# odrive-hat.net
KiCad netlist of a schematic drawn in EAGLE
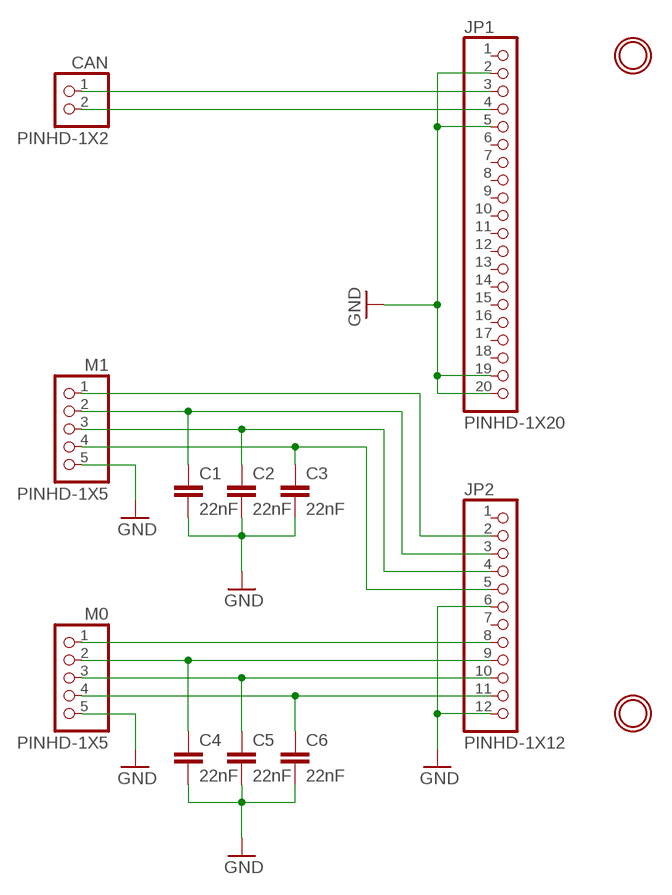
[diagram p0: schematic, sheet 1]

(export (version "E")
  (design (tool "Eeschema 10.0.6"))
  (components
    (comp (ref "C1")
      (value "22nF")
      (footprint "eagle-import:C0603")
      (libsource (lib "eagle-import") (part "C-EUC0603"))
    )
    (comp (ref "C2")
      (value "22nF")
      (footprint "eagle-import:C0603")
      (libsource (lib "eagle-import") (part "C-EUC0603"))
    )
    (comp (ref "C3")
      (value "22nF")
      (footprint "eagle-import:C0603")
      (libsource (lib "eagle-import") (part "C-EUC0603"))
    )
    (comp (ref "C4")
      (value "22nF")
      (footprint "eagle-import:C0603")
      (libsource (lib "eagle-import") (part "C-EUC0603"))
    )
    (comp (ref "C5")
      (value "22nF")
      (footprint "eagle-import:C0603")
      (libsource (lib "eagle-import") (part "C-EUC0603"))
    )
    (comp (ref "C6")
      (value "22nF")
      (footprint "eagle-import:C0603")
      (libsource (lib "eagle-import") (part "C-EUC0603"))
    )
    (comp (ref "CAN")
      (value "PINHD-1X2")
      (footprint "eagle-import:1X02")
      (libsource (lib "eagle-import") (part "PINHD-1X2"))
    )
    (comp (ref "JP1")
      (value "PINHD-1X20")
      (footprint "eagle-import:1X20")
      (libsource (lib "eagle-import") (part "PINHD-1X20"))
    )
    (comp (ref "JP2")
      (value "PINHD-1X12")
      (footprint "eagle-import:1X12")
      (libsource (lib "eagle-import") (part "PINHD-1X12"))
    )
    (comp (ref "M0")
      (value "PINHD-1X5")
      (footprint "eagle-import:1X05")
      (libsource (lib "eagle-import") (part "PINHD-1X5"))
    )
    (comp (ref "M1")
      (value "PINHD-1X5")
      (footprint "eagle-import:1X05")
      (libsource (lib "eagle-import") (part "PINHD-1X5"))
    )
    (comp (ref "U$1")
      (value "MICROBUILDER_MOUNTINGHOLE3.0THIN")
      (footprint "eagle-import:MICROBUILDER_MOUNTINGHOLE_3.0_PLATEDTHIN")
      (libsource (lib "eagle-import") (part "MICROBUILDER_MOUNTINGHOLE3.0THIN"))
    )
    (comp (ref "U$2")
      (value "MICROBUILDER_MOUNTINGHOLE3.0THIN")
      (footprint "eagle-import:MICROBUILDER_MOUNTINGHOLE_3.0_PLATEDTHIN")
      (libsource (lib "eagle-import") (part "MICROBUILDER_MOUNTINGHOLE3.0THIN"))
    )
  )
  (nets
    (net (code "1") (name "GND") (class "Default")
      (node (ref "C1") (pin "2") (pinfunction "2_2") (pintype "passive"))
      (node (ref "C2") (pin "2") (pinfunction "2_2") (pintype "passive"))
      (node (ref "C3") (pin "2") (pinfunction "2_2") (pintype "passive"))
      (node (ref "C4") (pin "2") (pinfunction "2_2") (pintype "passive"))
      (node (ref "C5") (pin "2") (pinfunction "2_2") (pintype "passive"))
      (node (ref "C6") (pin "2") (pinfunction "2_2") (pintype "passive"))
      (node (ref "JP1") (pin "19") (pinfunction "19_19") (pintype "passive"))
      (node (ref "JP1") (pin "2") (pinfunction "2_2") (pintype "passive"))
      (node (ref "JP1") (pin "20") (pinfunction "20_20") (pintype "passive"))
      (node (ref "JP1") (pin "5") (pinfunction "5_5") (pintype "passive"))
      (node (ref "JP2") (pin "12") (pinfunction "12_12") (pintype "passive"))
      (node (ref "JP2") (pin "6") (pinfunction "6_6") (pintype "passive"))
      (node (ref "M0") (pin "5") (pinfunction "5_5") (pintype "passive"))
      (node (ref "M1") (pin "5") (pinfunction "5_5") (pintype "passive"))
    )
    (net (code "2") (name "Net-(C1-Pad1)") (class "Default")
      (node (ref "C1") (pin "1") (pinfunction "1_1") (pintype "passive"))
      (node (ref "JP2") (pin "3") (pinfunction "3_3") (pintype "passive"))
      (node (ref "M1") (pin "2") (pinfunction "2_2") (pintype "passive"))
    )
    (net (code "3") (name "Net-(C2-Pad1)") (class "Default")
      (node (ref "C2") (pin "1") (pinfunction "1_1") (pintype "passive"))
      (node (ref "JP2") (pin "4") (pinfunction "4_4") (pintype "passive"))
      (node (ref "M1") (pin "3") (pinfunction "3_3") (pintype "passive"))
    )
    (net (code "4") (name "Net-(C3-Pad1)") (class "Default")
      (node (ref "C3") (pin "1") (pinfunction "1_1") (pintype "passive"))
      (node (ref "JP2") (pin "5") (pinfunction "5_5") (pintype "passive"))
      (node (ref "M1") (pin "4") (pinfunction "4_4") (pintype "passive"))
    )
    (net (code "5") (name "Net-(C4-Pad1)") (class "Default")
      (node (ref "C4") (pin "1") (pinfunction "1_1") (pintype "passive"))
      (node (ref "JP2") (pin "9") (pinfunction "9_9") (pintype "passive"))
      (node (ref "M0") (pin "2") (pinfunction "2_2") (pintype "passive"))
    )
    (net (code "6") (name "Net-(C5-Pad1)") (class "Default")
      (node (ref "C5") (pin "1") (pinfunction "1_1") (pintype "passive"))
      (node (ref "JP2") (pin "10") (pinfunction "10_10") (pintype "passive"))
      (node (ref "M0") (pin "3") (pinfunction "3_3") (pintype "passive"))
    )
    (net (code "7") (name "Net-(C6-Pad1)") (class "Default")
      (node (ref "C6") (pin "1") (pinfunction "1_1") (pintype "passive"))
      (node (ref "JP2") (pin "11") (pinfunction "11_11") (pintype "passive"))
      (node (ref "M0") (pin "4") (pinfunction "4_4") (pintype "passive"))
    )
    (net (code "8") (name "Net-(CAN-Pad1)") (class "Default")
      (node (ref "CAN") (pin "1") (pinfunction "1_1") (pintype "passive"))
      (node (ref "JP1") (pin "3") (pinfunction "3_3") (pintype "passive"))
    )
    (net (code "9") (name "Net-(CAN-Pad2)") (class "Default")
      (node (ref "CAN") (pin "2") (pinfunction "2_2") (pintype "passive"))
      (node (ref "JP1") (pin "4") (pinfunction "4_4") (pintype "passive"))
    )
    (net (code "10") (name "Net-(JP2-Pad2)") (class "Default")
      (node (ref "JP2") (pin "2") (pinfunction "2_2") (pintype "passive"))
      (node (ref "M1") (pin "1") (pinfunction "1_1") (pintype "passive"))
    )
    (net (code "11") (name "Net-(JP2-Pad8)") (class "Default")
      (node (ref "JP2") (pin "8") (pinfunction "8_8") (pintype "passive"))
      (node (ref "M0") (pin "1") (pinfunction "1_1") (pintype "passive"))
    )
    (net (code "12") (name "unconnected-(JP1-Pad1)") (class "Default")
      (node (ref "JP1") (pin "1") (pinfunction "1_1") (pintype "passive"))
    )
    (net (code "13") (name "unconnected-(JP1-Pad6)") (class "Default")
      (node (ref "JP1") (pin "6") (pinfunction "6_6") (pintype "passive"))
    )
    (net (code "14") (name "unconnected-(JP1-Pad7)") (class "Default")
      (node (ref "JP1") (pin "7") (pinfunction "7_7") (pintype "passive"))
    )
    (net (code "15") (name "unconnected-(JP1-Pad8)") (class "Default")
      (node (ref "JP1") (pin "8") (pinfunction "8_8") (pintype "passive"))
    )
    (net (code "16") (name "unconnected-(JP1-Pad9)") (class "Default")
      (node (ref "JP1") (pin "9") (pinfunction "9_9") (pintype "passive"))
    )
    (net (code "17") (name "unconnected-(JP1-Pad10)") (class "Default")
      (node (ref "JP1") (pin "10") (pinfunction "10_10") (pintype "passive"))
    )
    (net (code "18") (name "unconnected-(JP1-Pad11)") (class "Default")
      (node (ref "JP1") (pin "11") (pinfunction "11_11") (pintype "passive"))
    )
    (net (code "19") (name "unconnected-(JP1-Pad12)") (class "Default")
      (node (ref "JP1") (pin "12") (pinfunction "12_12") (pintype "passive"))
    )
    (net (code "20") (name "unconnected-(JP1-Pad13)") (class "Default")
      (node (ref "JP1") (pin "13") (pinfunction "13_13") (pintype "passive"))
    )
    (net (code "21") (name "unconnected-(JP1-Pad14)") (class "Default")
      (node (ref "JP1") (pin "14") (pinfunction "14_14") (pintype "passive"))
    )
    (net (code "22") (name "unconnected-(JP1-Pad15)") (class "Default")
      (node (ref "JP1") (pin "15") (pinfunction "15_15") (pintype "passive"))
    )
    (net (code "23") (name "unconnected-(JP1-Pad16)") (class "Default")
      (node (ref "JP1") (pin "16") (pinfunction "16_16") (pintype "passive"))
    )
    (net (code "24") (name "unconnected-(JP1-Pad17)") (class "Default")
      (node (ref "JP1") (pin "17") (pinfunction "17_17") (pintype "passive"))
    )
    (net (code "25") (name "unconnected-(JP1-Pad18)") (class "Default")
      (node (ref "JP1") (pin "18") (pinfunction "18_18") (pintype "passive"))
    )
    (net (code "26") (name "unconnected-(JP2-Pad1)") (class "Default")
      (node (ref "JP2") (pin "1") (pinfunction "1_1") (pintype "passive"))
    )
    (net (code "27") (name "unconnected-(JP2-Pad7)") (class "Default")
      (node (ref "JP2") (pin "7") (pinfunction "7_7") (pintype "passive"))
    )
  )
)
